# BGV1_0.net
KiCad netlist of a schematic drawn in Altium Designer
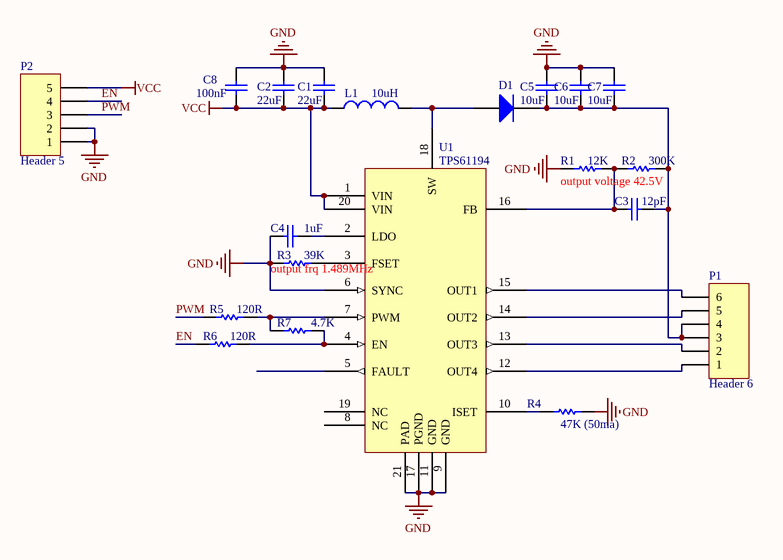
[diagram p0: BGV1.0.SchDoc]

(export (version "E")
  (design (tool "Eeschema 10.0.6"))
  (components
    (comp (ref "C1")
      (value "22uF")
      (footprint "3216[1206]")
      (description "Capacitor")
      (fields (field (name "Comment") "Cap") (field (name "PUBLISHER") "Altium Limited"))
      (libsource (lib "Miscellaneous Devices") (part "Cap"))
    )
    (comp (ref "C2")
      (value "22uF")
      (footprint "3216[1206]")
      (description "Capacitor")
      (fields (field (name "Comment") "Cap") (field (name "PUBLISHER") "Altium Limited"))
      (libsource (lib "Miscellaneous Devices") (part "Cap"))
    )
    (comp (ref "C3")
      (value "12pF")
      (footprint "0603")
      (description "Capacitor")
      (fields (field (name "Comment") "Cap") (field (name "PUBLISHER") "Altium Limited"))
      (libsource (lib "Miscellaneous Devices") (part "Cap"))
    )
    (comp (ref "C4")
      (value "1uF")
      (footprint "0603")
      (description "Capacitor")
      (fields (field (name "Comment") "Cap") (field (name "PUBLISHER") "Altium Limited"))
      (libsource (lib "Miscellaneous Devices") (part "Cap"))
    )
    (comp (ref "C5")
      (value "10uF")
      (footprint "3216[1206]")
      (description "Capacitor")
      (fields (field (name "Comment") "Cap") (field (name "PUBLISHER") "Altium Limited"))
      (libsource (lib "Miscellaneous Devices") (part "Cap"))
    )
    (comp (ref "C6")
      (value "10uF")
      (footprint "3216[1206]")
      (description "Capacitor")
      (fields (field (name "Comment") "Cap") (field (name "PUBLISHER") "Altium Limited"))
      (libsource (lib "Miscellaneous Devices") (part "Cap"))
    )
    (comp (ref "C7")
      (value "10uF")
      (footprint "3216[1206]")
      (description "Capacitor")
      (fields (field (name "Comment") "Cap") (field (name "PUBLISHER") "Altium Limited"))
      (libsource (lib "Miscellaneous Devices") (part "Cap"))
    )
    (comp (ref "C8")
      (value "100nF")
      (footprint "0603")
      (description "Capacitor")
      (fields (field (name "Comment") "Cap") (field (name "PUBLISHER") "Altium Limited"))
      (libsource (lib "Miscellaneous Devices") (part "Cap"))
    )
    (comp (ref "D1")
      (value "Diode 1N4448")
      (footprint "SMA")
      (description "High Conductance Fast Diode")
      (fields (field (name "PUBLISHER") "Altium Limited"))
      (libsource (lib "Miscellaneous Devices") (part "Diode 1N4448"))
    )
    (comp (ref "L1")
      (value "10uH")
      (footprint "L-6045")
      (description "Inductor")
      (fields (field (name "PUBLISHER") "Altium Limited"))
      (libsource (lib "Miscellaneous Devices") (part "Inductor"))
    )
    (comp (ref "P1")
      (value "Header 6")
      (footprint "1.25mm-6P")
      (description "Header, 6-Pin")
      (fields (field (name "PUBLISHER") "Altium Limited"))
      (libsource (lib "Miscellaneous Connectors") (part "Header 6"))
    )
    (comp (ref "P2")
      (value "Header 5")
      (footprint "PH2.0-5P-SMT")
      (description "Header, 5-Pin")
      (fields (field (name "PUBLISHER") "Altium Limited"))
      (libsource (lib "Miscellaneous Connectors") (part "Header 5"))
    )
    (comp (ref "R1")
      (value "12K")
      (footprint "0603")
      (description "Resistor")
      (fields (field (name "Comment") "Res1") (field (name "PUBLISHER") "Altium Limited"))
      (libsource (lib "Miscellaneous Devices") (part "Res1"))
    )
    (comp (ref "R2")
      (value "300K")
      (footprint "0603")
      (description "Resistor")
      (fields (field (name "Comment") "Res1") (field (name "PUBLISHER") "Altium Limited"))
      (libsource (lib "Miscellaneous Devices") (part "Res1"))
    )
    (comp (ref "R3")
      (value "39K")
      (footprint "0603")
      (description "Resistor")
      (fields (field (name "Comment") "Res1") (field (name "PUBLISHER") "Altium Limited"))
      (libsource (lib "Miscellaneous Devices") (part "Res1"))
    )
    (comp (ref "R4")
      (value "47K (50ma)")
      (footprint "0603")
      (description "Resistor")
      (fields (field (name "Comment") "Res1") (field (name "PUBLISHER") "Altium Limited"))
      (libsource (lib "Miscellaneous Devices") (part "Res1"))
    )
    (comp (ref "R5")
      (value "120R")
      (footprint "0603")
      (description "Resistor")
      (fields (field (name "Comment") "Res1") (field (name "PUBLISHER") "Altium Limited"))
      (libsource (lib "Miscellaneous Devices") (part "Res1"))
    )
    (comp (ref "R6")
      (value "120R")
      (footprint "0603")
      (description "Resistor")
      (fields (field (name "Comment") "Res1") (field (name "PUBLISHER") "Altium Limited"))
      (libsource (lib "Miscellaneous Devices") (part "Res1"))
    )
    (comp (ref "R7")
      (value "4.7K")
      (footprint "0402")
      (description "Resistor")
      (fields (field (name "Comment") "Res1") (field (name "PUBLISHER") "Altium Limited"))
      (libsource (lib "Miscellaneous Devices") (part "Res1"))
    )
    (comp (ref "U1") (value "TPS61194") (footprint "HTTSOP-20") (libsource (lib "TANK") (part "TPS61194")))
  )
  (nets
    (net (code "1") (name "/EN") (class "Default")
      (node (ref "P2") (pin "4") (pinfunction "4_4") (pintype "passive"))
      (node (ref "R6") (pin "2") (pinfunction "2_2") (pintype "passive"))
    )
    (net (code "2") (name "/PWM") (class "Default")
      (node (ref "P2") (pin "3") (pinfunction "3_3") (pintype "passive"))
      (node (ref "R5") (pin "2") (pinfunction "2_2") (pintype "passive"))
    )
    (net (code "3") (name "GND") (class "Default")
      (node (ref "C1") (pin "1") (pinfunction "1_1") (pintype "passive"))
      (node (ref "C2") (pin "1") (pinfunction "1_1") (pintype "passive"))
      (node (ref "C4") (pin "1") (pinfunction "1_1") (pintype "passive"))
      (node (ref "C5") (pin "1") (pinfunction "1_1") (pintype "passive"))
      (node (ref "C6") (pin "1") (pinfunction "1_1") (pintype "passive"))
      (node (ref "C7") (pin "1") (pinfunction "1_1") (pintype "passive"))
      (node (ref "C8") (pin "2") (pinfunction "2_2") (pintype "passive"))
      (node (ref "P2") (pin "1") (pinfunction "1_1") (pintype "passive"))
      (node (ref "P2") (pin "2") (pinfunction "2_2") (pintype "passive"))
      (node (ref "R1") (pin "1") (pinfunction "1_1") (pintype "passive"))
      (node (ref "R3") (pin "1") (pinfunction "1_1") (pintype "passive"))
      (node (ref "R4") (pin "2") (pinfunction "2_2") (pintype "passive"))
      (node (ref "U1") (pin "11") (pinfunction "GND_11") (pintype "passive"))
      (node (ref "U1") (pin "17") (pinfunction "PGND_17") (pintype "passive"))
      (node (ref "U1") (pin "21") (pinfunction "PAD_21") (pintype "passive"))
      (node (ref "U1") (pin "6") (pinfunction "SYNC_6") (pintype "input"))
      (node (ref "U1") (pin "9") (pinfunction "GND_9") (pintype "passive"))
    )
    (net (code "4") (name "Net-(D1-A)") (class "Default")
      (node (ref "D1") (pin "1") (pinfunction "A_1") (pintype "passive"))
      (node (ref "L1") (pin "2") (pinfunction "2_2") (pintype "passive"))
      (node (ref "U1") (pin "18") (pinfunction "SW_18") (pintype "passive"))
    )
    (net (code "5") (name "Net-(D1-K)") (class "Default")
      (node (ref "C3") (pin "2") (pinfunction "2_2") (pintype "passive"))
      (node (ref "C5") (pin "2") (pinfunction "2_2") (pintype "passive"))
      (node (ref "C6") (pin "2") (pinfunction "2_2") (pintype "passive"))
      (node (ref "C7") (pin "2") (pinfunction "2_2") (pintype "passive"))
      (node (ref "D1") (pin "2") (pinfunction "K_2") (pintype "passive"))
      (node (ref "P1") (pin "3") (pinfunction "3_3") (pintype "passive"))
      (node (ref "P1") (pin "4") (pinfunction "4_4") (pintype "passive"))
      (node (ref "R2") (pin "2") (pinfunction "2_2") (pintype "passive"))
    )
    (net (code "6") (name "Net-(U1-EN)") (class "Default")
      (node (ref "R6") (pin "1") (pinfunction "1_1") (pintype "passive"))
      (node (ref "R7") (pin "2") (pinfunction "2_2") (pintype "passive"))
      (node (ref "U1") (pin "4") (pinfunction "EN_4") (pintype "input"))
    )
    (net (code "7") (name "Net-(U1-FB)") (class "Default")
      (node (ref "C3") (pin "1") (pinfunction "1_1") (pintype "passive"))
      (node (ref "R1") (pin "2") (pinfunction "2_2") (pintype "passive"))
      (node (ref "R2") (pin "1") (pinfunction "1_1") (pintype "passive"))
      (node (ref "U1") (pin "16") (pinfunction "FB_16") (pintype "passive"))
    )
    (net (code "8") (name "Net-(U1-FSET)") (class "Default")
      (node (ref "R3") (pin "2") (pinfunction "2_2") (pintype "passive"))
      (node (ref "U1") (pin "3") (pinfunction "FSET_3") (pintype "passive"))
    )
    (net (code "9") (name "Net-(U1-ISET)") (class "Default")
      (node (ref "R4") (pin "1") (pinfunction "1_1") (pintype "passive"))
      (node (ref "U1") (pin "10") (pinfunction "ISET_10") (pintype "passive"))
    )
    (net (code "10") (name "Net-(U1-LDO)") (class "Default")
      (node (ref "C4") (pin "2") (pinfunction "2_2") (pintype "passive"))
      (node (ref "U1") (pin "2") (pinfunction "LDO_2") (pintype "passive"))
    )
    (net (code "11") (name "Net-(U1-OUT1)") (class "Default")
      (node (ref "P1") (pin "6") (pinfunction "6_6") (pintype "passive"))
      (node (ref "U1") (pin "15") (pinfunction "OUT1_15") (pintype "output"))
    )
    (net (code "12") (name "Net-(U1-OUT2)") (class "Default")
      (node (ref "P1") (pin "5") (pinfunction "5_5") (pintype "passive"))
      (node (ref "U1") (pin "14") (pinfunction "OUT2_14") (pintype "output"))
    )
    (net (code "13") (name "Net-(U1-OUT3)") (class "Default")
      (node (ref "P1") (pin "2") (pinfunction "2_2") (pintype "passive"))
      (node (ref "U1") (pin "13") (pinfunction "OUT3_13") (pintype "output"))
    )
    (net (code "14") (name "Net-(U1-OUT4)") (class "Default")
      (node (ref "P1") (pin "1") (pinfunction "1_1") (pintype "passive"))
      (node (ref "U1") (pin "12") (pinfunction "OUT4_12") (pintype "output"))
    )
    (net (code "15") (name "Net-(U1-PWM)") (class "Default")
      (node (ref "R5") (pin "1") (pinfunction "1_1") (pintype "passive"))
      (node (ref "R7") (pin "1") (pinfunction "1_1") (pintype "passive"))
      (node (ref "U1") (pin "7") (pinfunction "PWM_7") (pintype "input"))
    )
    (net (code "16") (name "VCC") (class "Default")
      (node (ref "C1") (pin "2") (pinfunction "2_2") (pintype "passive"))
      (node (ref "C2") (pin "2") (pinfunction "2_2") (pintype "passive"))
      (node (ref "C8") (pin "1") (pinfunction "1_1") (pintype "passive"))
      (node (ref "L1") (pin "1") (pinfunction "1_1") (pintype "passive"))
      (node (ref "P2") (pin "5") (pinfunction "5_5") (pintype "passive"))
      (node (ref "U1") (pin "1") (pinfunction "VIN_1") (pintype "passive"))
      (node (ref "U1") (pin "20") (pinfunction "VIN_20") (pintype "passive"))
    )
    (net (code "17") (name "unconnected-(U1-FAULT-Pad5)") (class "Default")
      (node (ref "U1") (pin "5") (pinfunction "FAULT_5") (pintype "output"))
    )
    (net (code "18") (name "unconnected-(U1-NC-Pad8)") (class "Default")
      (node (ref "U1") (pin "8") (pinfunction "NC_8") (pintype "passive"))
    )
    (net (code "19") (name "unconnected-(U1-NC-Pad19)") (class "Default")
      (node (ref "U1") (pin "19") (pinfunction "NC_19") (pintype "passive"))
    )
  )
)
